# USB_Interruptor.net
KiCad netlist of a schematic drawn in Altium Designer
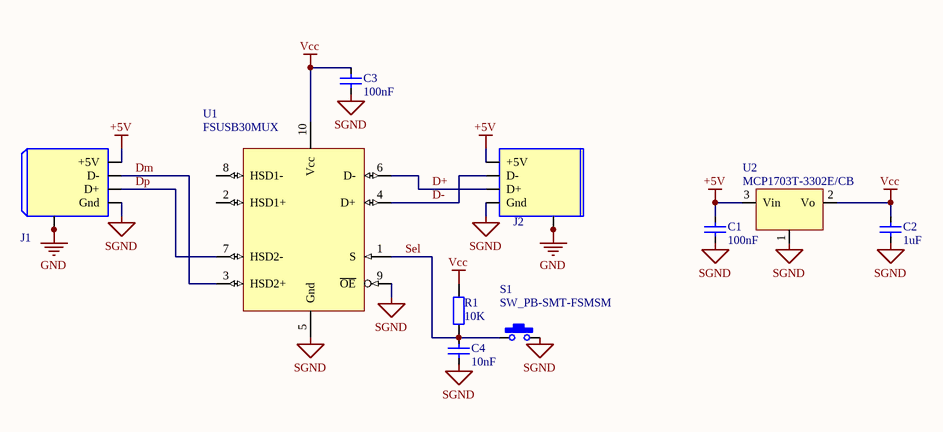
[diagram p0: USB_Interruptor.SchDoc]

(export (version "E")
  (design (tool "Eeschema 10.0.6"))
  (components
    (comp (ref "C1")
      (value "100nF")
      (footprint "CCNP2012-0805")
      (description "Capacitor SMT 0805")
      (fields
        (field (name "MANUFACTURER") "Generic Components")
        (field (name "PUBLISHER") "Altium Hobart Technology Centre")
      )
      (libsource (lib "MyLibrary") (part "Cap_CCNP_0805"))
    )
    (comp (ref "C2")
      (value "1uF")
      (footprint "CCNP2012-0805")
      (description "Capacitor SMT 0805")
      (fields
        (field (name "MANUFACTURER") "Generic Components")
        (field (name "PUBLISHER") "Altium Hobart Technology Centre")
      )
      (libsource (lib "MyLibrary") (part "Cap_CCNP_0805"))
    )
    (comp (ref "C3")
      (value "100nF")
      (footprint "CCNP2012-0805")
      (description "Capacitor SMT 0805")
      (fields
        (field (name "MANUFACTURER") "Generic Components")
        (field (name "PUBLISHER") "Altium Hobart Technology Centre")
      )
      (libsource (lib "MyLibrary") (part "Cap_CCNP_0805"))
    )
    (comp (ref "C4")
      (value "10nF")
      (footprint "CCNP2012-0805")
      (description "Capacitor SMT 0805")
      (fields
        (field (name "MANUFACTURER") "Generic Components")
        (field (name "PUBLISHER") "Altium Hobart Technology Centre")
      )
      (libsource (lib "MyLibrary") (part "Cap_CCNP_0805"))
    )
    (comp (ref "J1")
      (value "USB Type A Plug")
      (footprint "USB_TypeA Plug")
      (description "MOLEX 48037-1000")
      (libsource (lib "MyLibrary") (part "USB_TYPE_A_PLUG"))
    )
    (comp (ref "J2")
      (value "USB Type A Socket")
      (footprint "USB-A-Socket")
      (description "AMPHENOL FCI  87520-0010BLF")
      (libsource (lib "MySchLib") (part "USB_TYPE_A_SOCKET"))
    )
    (comp (ref "R1")
      (value "10K")
      (footprint "CR2012-0805")
      (description "Resistor")
      (fields
        (field (name "MANUFACTURER") "Generic Components")
        (field (name "PUBLISHER") "Altium Hobart Technology Centre")
      )
      (libsource (lib "MyLibrary") (part "Res_CR0805"))
    )
    (comp (ref "S1")
      (value "SW_PB-SMT-FSMSM")
      (footprint "SW_MIN_PB-FSMSM")
      (description "SWITCH, TACTILE SPST 50mA, SMD GULL WING")
      (fields (field (name "MANUFACTURER") "Generic Components") (field (name "PUBLISHER") "Altium Limited"))
      (libsource (lib "MyLibrary") (part "SW_PB-SMT-FSMSM"))
    )
    (comp (ref "U1")
      (value "FSUSB30MUX")
      (footprint "MSOP-10")
      (description "USB Switch")
      (libsource (lib "MySchLib") (part "FSUSB30"))
    )
    (comp (ref "U2")
      (value "MCP1703T-3302E/CB")
      (footprint "SOT23")
      (description "3V3 LDO regulator")
      (libsource (lib "MyLibrary") (part "MCP1703T-3302E/CB"))
    )
  )
  (nets
    (net (code "1") (name "+5V") (class "Default")
      (node (ref "C1") (pin "1") (pinfunction "1_1") (pintype "passive"))
      (node (ref "J1") (pin "5V") (pinfunction "+5V_5V") (pintype "power_in"))
      (node (ref "J2") (pin "5V") (pinfunction "+5V_5V") (pintype "power_in"))
      (node (ref "U2") (pin "3") (pinfunction "Vin_3") (pintype "passive"))
    )
    (net (code "2") (name "/D+") (class "Default")
      (node (ref "J2") (pin "D+") (pinfunction "D+_D+") (pintype "passive"))
      (node (ref "U1") (pin "6") (pinfunction "D-_6") (pintype "bidirectional"))
    )
    (net (code "3") (name "/D-") (class "Default")
      (node (ref "J2") (pin "D-") (pinfunction "D-_D-") (pintype "passive"))
      (node (ref "U1") (pin "4") (pinfunction "D+_4") (pintype "bidirectional"))
    )
    (net (code "4") (name "/Dm") (class "Default")
      (node (ref "J1") (pin "D-") (pinfunction "D-_D-") (pintype "passive"))
      (node (ref "U1") (pin "3") (pinfunction "HSD2+_3") (pintype "bidirectional"))
    )
    (net (code "5") (name "/Dp") (class "Default")
      (node (ref "J1") (pin "D+") (pinfunction "D+_D+") (pintype "passive"))
      (node (ref "U1") (pin "7") (pinfunction "HSD2-_7") (pintype "bidirectional"))
    )
    (net (code "6") (name "/Sel") (class "Default")
      (node (ref "C4") (pin "1") (pinfunction "1_1") (pintype "passive"))
      (node (ref "R1") (pin "1") (pinfunction "1_1") (pintype "passive"))
      (node (ref "S1") (pin "1") (pinfunction "1_1") (pintype "passive"))
      (node (ref "U1") (pin "1") (pinfunction "S_1") (pintype "input"))
    )
    (net (code "7") (name "GND") (class "Default")
      (node (ref "J1") (pin "Shield1") (pinfunction "USBShd_Shield1") (pintype "passive"))
      (node (ref "J1") (pin "Shield2") (pinfunction "USBShd_Shield2") (pintype "passive"))
      (node (ref "J2") (pin "Shield1") (pinfunction "USBShd_Shield1") (pintype "passive"))
      (node (ref "J2") (pin "Shield2") (pinfunction "USBShd_Shield2") (pintype "passive"))
    )
    (net (code "8") (name "SGND") (class "Default")
      (node (ref "C1") (pin "2") (pinfunction "2_2") (pintype "passive"))
      (node (ref "C2") (pin "1") (pinfunction "1_1") (pintype "passive"))
      (node (ref "C3") (pin "2") (pinfunction "2_2") (pintype "passive"))
      (node (ref "C4") (pin "2") (pinfunction "2_2") (pintype "passive"))
      (node (ref "J1") (pin "Gnd") (pinfunction "Gnd_Gnd") (pintype "passive"))
      (node (ref "J2") (pin "Gnd") (pinfunction "Gnd_Gnd") (pintype "passive"))
      (node (ref "S1") (pin "2") (pinfunction "2_2") (pintype "passive"))
      (node (ref "U1") (pin "5") (pinfunction "Gnd_5") (pintype "power_in"))
      (node (ref "U1") (pin "9") (pinfunction "~{OE}_9") (pintype "input"))
      (node (ref "U2") (pin "1") (pinfunction "Gnd_1") (pintype "passive"))
    )
    (net (code "9") (name "Vcc") (class "Default")
      (node (ref "C2") (pin "2") (pinfunction "2_2") (pintype "passive"))
      (node (ref "C3") (pin "1") (pinfunction "1_1") (pintype "passive"))
      (node (ref "R1") (pin "2") (pinfunction "2_2") (pintype "passive"))
      (node (ref "U1") (pin "10") (pinfunction "Vcc_10") (pintype "power_in"))
      (node (ref "U2") (pin "2") (pinfunction "Vo_2") (pintype "passive"))
    )
    (net (code "10") (name "unconnected-(U1-HSD1+-Pad2)") (class "Default")
      (node (ref "U1") (pin "2") (pinfunction "HSD1+_2") (pintype "bidirectional"))
    )
    (net (code "11") (name "unconnected-(U1-HSD1--Pad8)") (class "Default")
      (node (ref "U1") (pin "8") (pinfunction "HSD1-_8") (pintype "bidirectional"))
    )
  )
)
